# MSS_IO.net
KiCad netlist of a schematic drawn in Altium Designer
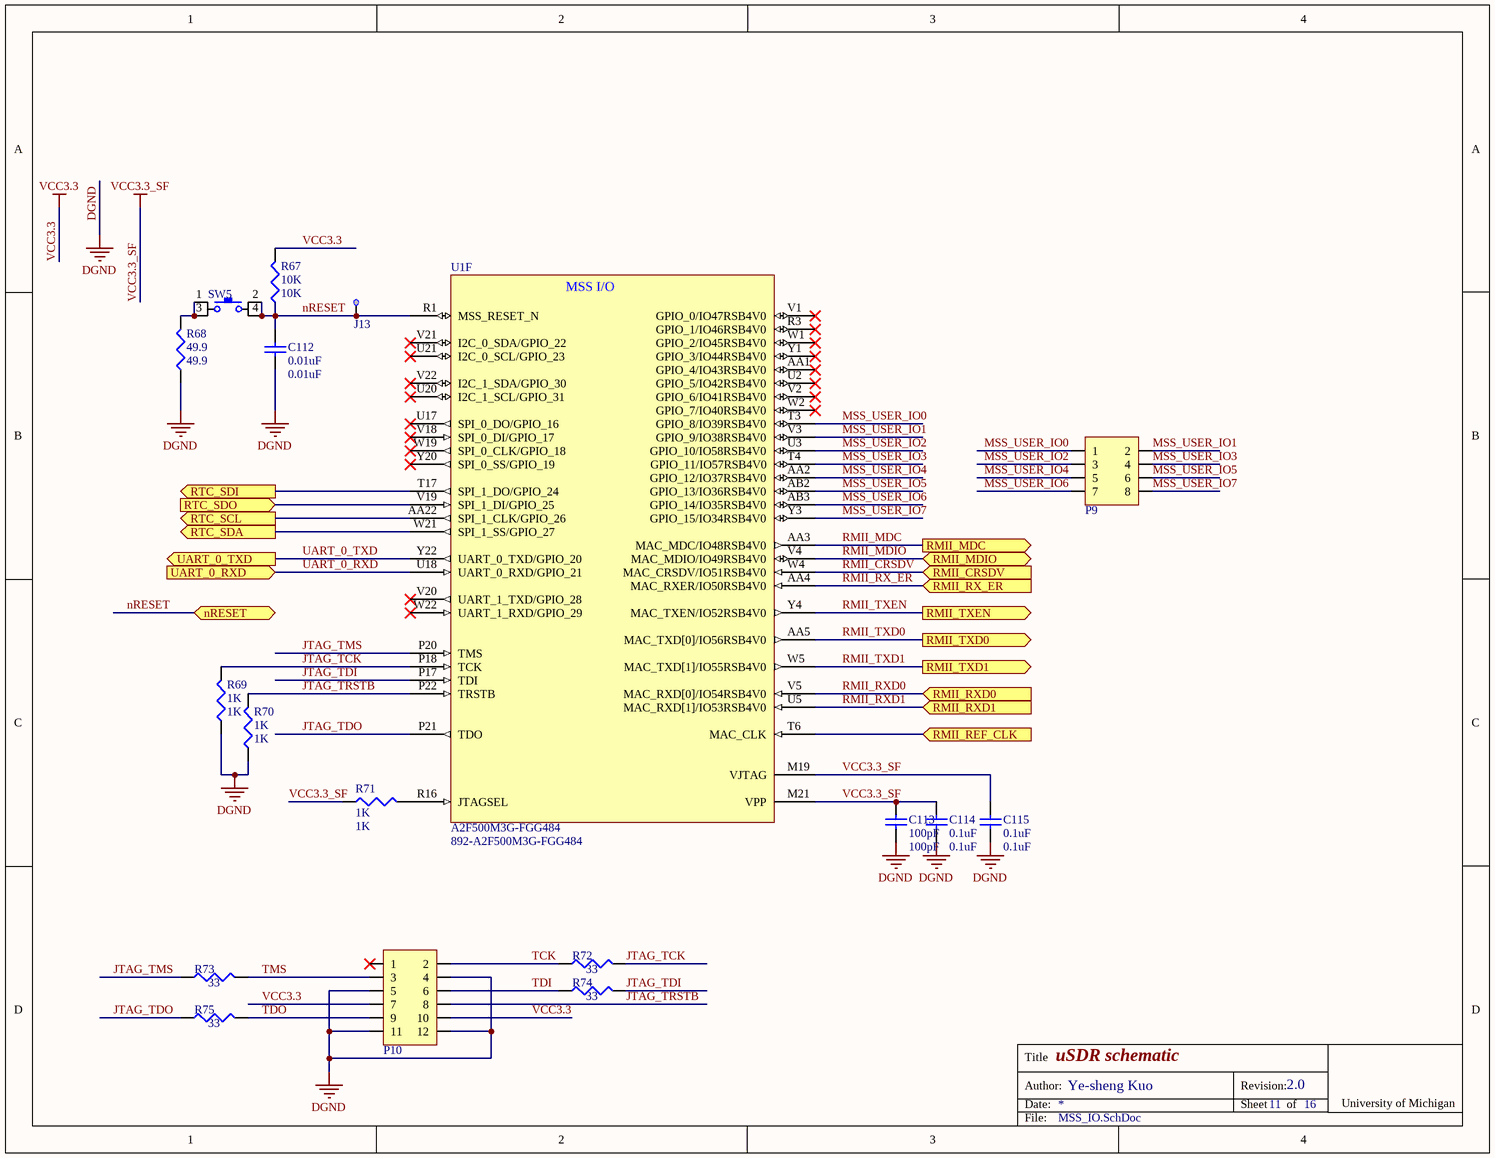
[diagram p0: MSS_IO.SchDoc]

(export (version "E")
  (design (tool "Eeschema 10.0.6"))
  (components
    (comp (ref "C112")
      (value "0.01uF")
      (footprint "0402")
      (description "Capacitor (Semiconductor SIM Model)")
      (fields (field (name "ALTIUM_VALUE") "0.01uF") (field (name "PUBLISHER") "Altium Limited"))
      (libsource (lib "Miscellaneous Devices") (part "Cap Semi"))
    )
    (comp (ref "C113")
      (value "100pF")
      (footprint "0402")
      (description "Capacitor (Semiconductor SIM Model)")
      (fields (field (name "ALTIUM_VALUE") "100pF") (field (name "PUBLISHER") "Altium Limited"))
      (libsource (lib "Miscellaneous Devices") (part "Cap Semi"))
    )
    (comp (ref "C114")
      (value "0.1uF")
      (footprint "0402")
      (description "Capacitor (Semiconductor SIM Model)")
      (fields (field (name "ALTIUM_VALUE") "0.1uF") (field (name "PUBLISHER") "Altium Limited"))
      (libsource (lib "Miscellaneous Devices") (part "Cap Semi"))
    )
    (comp (ref "C115")
      (value "0.1uF")
      (footprint "0402")
      (description "Capacitor (Semiconductor SIM Model)")
      (fields (field (name "ALTIUM_VALUE") "0.1uF") (field (name "PUBLISHER") "Altium Limited"))
      (libsource (lib "Miscellaneous Devices") (part "Cap Semi"))
    )
    (comp (ref "J13")
      (value "5004")
      (footprint "TestPoint")
      (description "TEST POINT PC MINI .040\"D YELLOW")
      (libsource (lib "SDR") (part "TestPoint"))
    )
    (comp (ref "P9")
      (value "2 x 4 header")
      (footprint "2x4 header")
      (description "100 mils standard header")
      (libsource (lib "SDR") (part "2 x 4 header"))
    )
    (comp (ref "P10")
      (value "2 x 6 header")
      (footprint "2x6 header, right angle")
      (description "100 mils standard header")
      (libsource (lib "SDR") (part "2 x 6 header"))
    )
    (comp (ref "R67")
      (value "10K")
      (footprint "0402")
      (description "Resistor")
      (fields (field (name "ALTIUM_VALUE") "10K") (field (name "PUBLISHER") "Altium Limited"))
      (libsource (lib "Miscellaneous Devices") (part "Res3"))
    )
    (comp (ref "R68")
      (value "49.9")
      (footprint "0402")
      (description "Resistor")
      (fields (field (name "ALTIUM_VALUE") "49.9") (field (name "PUBLISHER") "Altium Limited"))
      (libsource (lib "Miscellaneous Devices") (part "Res3"))
    )
    (comp (ref "R69")
      (value "1K")
      (footprint "0402")
      (description "Resistor")
      (fields (field (name "ALTIUM_VALUE") "1K") (field (name "PUBLISHER") "Altium Limited"))
      (libsource (lib "Miscellaneous Devices") (part "Res3"))
    )
    (comp (ref "R70")
      (value "1K")
      (footprint "0402")
      (description "Resistor")
      (fields (field (name "ALTIUM_VALUE") "1K") (field (name "PUBLISHER") "Altium Limited"))
      (libsource (lib "Miscellaneous Devices") (part "Res3"))
    )
    (comp (ref "R71")
      (value "1K")
      (footprint "0402")
      (description "Resistor")
      (fields (field (name "ALTIUM_VALUE") "1K") (field (name "PUBLISHER") "Altium Limited"))
      (libsource (lib "Miscellaneous Devices") (part "Res3"))
    )
    (comp (ref "R72")
      (value "33")
      (footprint "0402")
      (description "Resistor")
      (fields (field (name "PUBLISHER") "Altium Limited"))
      (libsource (lib "Miscellaneous Devices") (part "Res3"))
    )
    (comp (ref "R73")
      (value "33")
      (footprint "0402")
      (description "Resistor")
      (fields (field (name "PUBLISHER") "Altium Limited"))
      (libsource (lib "Miscellaneous Devices") (part "Res3"))
    )
    (comp (ref "R74")
      (value "33")
      (footprint "0402")
      (description "Resistor")
      (fields (field (name "PUBLISHER") "Altium Limited"))
      (libsource (lib "Miscellaneous Devices") (part "Res3"))
    )
    (comp (ref "R75")
      (value "33")
      (footprint "0402")
      (description "Resistor")
      (fields (field (name "PUBLISHER") "Altium Limited"))
      (libsource (lib "Miscellaneous Devices") (part "Res3"))
    )
    (comp (ref "SW5")
      (value "Switch 4-lead")
      (footprint "EVQPA PB")
      (description "Switch")
      (libsource (lib "SDR") (part "Switch 4-lead"))
    )
    (comp (ref "U1")
      (value "A2F500M3G-FGG484")
      (footprint "BGA100P22X22-484N")
      (description "FPGA - Field Programmable Gate Array 500K System Gates")
      (fields (field (name "SUPPLIER PART NUMBER 1") "892-A2F500M3G-FGG484"))
      (libsource (lib "SDR") (part "F2-200_500-FGG484_1"))
    )
  )
  (nets
    (net (code "1") (name "/JTAG_TCK") (class "Default")
      (node (ref "R69") (pin "2") (pinfunction "2_2") (pintype "passive"))
      (node (ref "R72") (pin "2") (pinfunction "2_2") (pintype "passive"))
      (node (ref "U1") (pin "P18") (pinfunction "TCK_P18") (pintype "input"))
    )
    (net (code "2") (name "/JTAG_TDI") (class "Default")
      (node (ref "R74") (pin "2") (pinfunction "2_2") (pintype "passive"))
      (node (ref "U1") (pin "P17") (pinfunction "TDI_P17") (pintype "input"))
    )
    (net (code "3") (name "/JTAG_TDO") (class "Default")
      (node (ref "R75") (pin "1") (pinfunction "1_1") (pintype "passive"))
      (node (ref "U1") (pin "P21") (pinfunction "TDO_P21") (pintype "output"))
    )
    (net (code "4") (name "/JTAG_TMS") (class "Default")
      (node (ref "R73") (pin "1") (pinfunction "1_1") (pintype "passive"))
      (node (ref "U1") (pin "P20") (pinfunction "TMS_P20") (pintype "input"))
    )
    (net (code "5") (name "/JTAG_TRSTB") (class "Default")
      (node (ref "P10") (pin "8") (pinfunction "8_8") (pintype "passive"))
      (node (ref "R70") (pin "2") (pinfunction "2_2") (pintype "passive"))
      (node (ref "U1") (pin "P22") (pinfunction "TRSTB_P22") (pintype "input"))
    )
    (net (code "6") (name "/MSS_USER_IO0") (class "Default")
      (node (ref "P9") (pin "1") (pinfunction "1_1") (pintype "passive"))
      (node (ref "U1") (pin "T3") (pinfunction "GPIO_8/IO39RSB4V0_T3") (pintype "bidirectional"))
    )
    (net (code "7") (name "/MSS_USER_IO1") (class "Default")
      (node (ref "P9") (pin "2") (pinfunction "2_2") (pintype "passive"))
      (node (ref "U1") (pin "V3") (pinfunction "GPIO_9/IO38RSB4V0_V3") (pintype "bidirectional"))
    )
    (net (code "8") (name "/MSS_USER_IO2") (class "Default")
      (node (ref "P9") (pin "3") (pinfunction "3_3") (pintype "passive"))
      (node (ref "U1") (pin "U3") (pinfunction "GPIO_10/IO58RSB4V0_U3") (pintype "bidirectional"))
    )
    (net (code "9") (name "/MSS_USER_IO3") (class "Default")
      (node (ref "P9") (pin "4") (pinfunction "4_4") (pintype "passive"))
      (node (ref "U1") (pin "T4") (pinfunction "GPIO_11/IO57RSB4V0_T4") (pintype "bidirectional"))
    )
    (net (code "10") (name "/MSS_USER_IO4") (class "Default")
      (node (ref "P9") (pin "5") (pinfunction "5_5") (pintype "passive"))
      (node (ref "U1") (pin "AA2") (pinfunction "GPIO_12/IO37RSB4V0_AA2") (pintype "bidirectional"))
    )
    (net (code "11") (name "/MSS_USER_IO5") (class "Default")
      (node (ref "P9") (pin "6") (pinfunction "6_6") (pintype "passive"))
      (node (ref "U1") (pin "AB2") (pinfunction "GPIO_13/IO36RSB4V0_AB2") (pintype "bidirectional"))
    )
    (net (code "12") (name "/MSS_USER_IO6") (class "Default")
      (node (ref "P9") (pin "7") (pinfunction "7_7") (pintype "passive"))
      (node (ref "U1") (pin "AB3") (pinfunction "GPIO_14/IO35RSB4V0_AB3") (pintype "bidirectional"))
    )
    (net (code "13") (name "/MSS_USER_IO7") (class "Default")
      (node (ref "P9") (pin "8") (pinfunction "8_8") (pintype "passive"))
      (node (ref "U1") (pin "Y3") (pinfunction "GPIO_15/IO34RSB4V0_Y3") (pintype "bidirectional"))
    )
    (net (code "14") (name "/RMII_CRSDV") (class "Default")
      (node (ref "U1") (pin "W4") (pinfunction "MAC_CRSDV/IO51RSB4V0_W4") (pintype "input"))
    )
    (net (code "15") (name "/RMII_MDC") (class "Default")
      (node (ref "U1") (pin "AA3") (pinfunction "MAC_MDC/IO48RSB4V0_AA3") (pintype "output"))
    )
    (net (code "16") (name "/RMII_MDIO") (class "Default")
      (node (ref "U1") (pin "V4") (pinfunction "MAC_MDIO/IO49RSB4V0_V4") (pintype "bidirectional"))
    )
    (net (code "17") (name "/RMII_REF_CLK") (class "Default")
      (node (ref "U1") (pin "T6") (pinfunction "MAC_CLK_T6") (pintype "input"))
    )
    (net (code "18") (name "/RMII_RXD0") (class "Default")
      (node (ref "U1") (pin "V5") (pinfunction "MAC_RXD[0]/IO54RSB4V0_V5") (pintype "input"))
    )
    (net (code "19") (name "/RMII_RXD1") (class "Default")
      (node (ref "U1") (pin "U5") (pinfunction "MAC_RXD[1]/IO53RSB4V0_U5") (pintype "input"))
    )
    (net (code "20") (name "/RMII_RX_ER") (class "Default")
      (node (ref "U1") (pin "AA4") (pinfunction "MAC_RXER/IO50RSB4V0_AA4") (pintype "input"))
    )
    (net (code "21") (name "/RMII_TXD0") (class "Default")
      (node (ref "U1") (pin "AA5") (pinfunction "MAC_TXD[0]/IO56RSB4V0_AA5") (pintype "output"))
    )
    (net (code "22") (name "/RMII_TXD1") (class "Default")
      (node (ref "U1") (pin "W5") (pinfunction "MAC_TXD[1]/IO55RSB4V0_W5") (pintype "output"))
    )
    (net (code "23") (name "/RMII_TXEN") (class "Default")
      (node (ref "U1") (pin "Y4") (pinfunction "MAC_TXEN/IO52RSB4V0_Y4") (pintype "output"))
    )
    (net (code "24") (name "/RTC_SCL") (class "Default")
      (node (ref "U1") (pin "AA22") (pinfunction "SPI_1_CLK/GPIO_26_AA22") (pintype "output"))
    )
    (net (code "25") (name "/RTC_SDA") (class "Default")
      (node (ref "U1") (pin "W21") (pinfunction "SPI_1_SS/GPIO_27_W21") (pintype "output"))
    )
    (net (code "26") (name "/RTC_SDI") (class "Default")
      (node (ref "U1") (pin "T17") (pinfunction "SPI_1_DO/GPIO_24_T17") (pintype "output"))
    )
    (net (code "27") (name "/RTC_SDO") (class "Default")
      (node (ref "U1") (pin "V19") (pinfunction "SPI_1_DI/GPIO_25_V19") (pintype "input"))
    )
    (net (code "28") (name "/TCK") (class "Default")
      (node (ref "P10") (pin "2") (pinfunction "2_2") (pintype "passive"))
      (node (ref "R72") (pin "1") (pinfunction "1_1") (pintype "passive"))
    )
    (net (code "29") (name "/TDI") (class "Default")
      (node (ref "P10") (pin "6") (pinfunction "6_6") (pintype "passive"))
      (node (ref "R74") (pin "1") (pinfunction "1_1") (pintype "passive"))
    )
    (net (code "30") (name "/TDO") (class "Default")
      (node (ref "P10") (pin "9") (pinfunction "9_9") (pintype "passive"))
      (node (ref "R75") (pin "2") (pinfunction "2_2") (pintype "passive"))
    )
    (net (code "31") (name "/TMS") (class "Default")
      (node (ref "P10") (pin "3") (pinfunction "3_3") (pintype "passive"))
      (node (ref "R73") (pin "2") (pinfunction "2_2") (pintype "passive"))
    )
    (net (code "32") (name "/UART_0_RXD") (class "Default")
      (node (ref "U1") (pin "U18") (pinfunction "UART_0_RXD/GPIO_21_U18") (pintype "input"))
    )
    (net (code "33") (name "/UART_0_TXD") (class "Default")
      (node (ref "U1") (pin "Y22") (pinfunction "UART_0_TXD/GPIO_20_Y22") (pintype "output"))
    )
    (net (code "34") (name "/nRESET") (class "Default")
      (node (ref "C112") (pin "2") (pinfunction "2_2") (pintype "passive"))
      (node (ref "J13") (pin "1") (pinfunction "TB_1") (pintype "passive"))
      (node (ref "R67") (pin "1") (pinfunction "1_1") (pintype "passive"))
      (node (ref "SW5") (pin "2") (pinfunction "2_2") (pintype "passive"))
      (node (ref "SW5") (pin "4") (pinfunction "4_4") (pintype "passive"))
      (node (ref "U1") (pin "R1") (pinfunction "MSS_RESET_N_R1") (pintype "bidirectional"))
    )
    (net (code "35") (name "DGND") (class "Default")
      (node (ref "C112") (pin "1") (pinfunction "1_1") (pintype "passive"))
      (node (ref "C113") (pin "1") (pinfunction "1_1") (pintype "passive"))
      (node (ref "C114") (pin "1") (pinfunction "1_1") (pintype "passive"))
      (node (ref "C115") (pin "1") (pinfunction "1_1") (pintype "passive"))
      (node (ref "P10") (pin "11") (pinfunction "11_11") (pintype "passive"))
      (node (ref "P10") (pin "12") (pinfunction "12_12") (pintype "passive"))
      (node (ref "P10") (pin "4") (pinfunction "4_4") (pintype "passive"))
      (node (ref "P10") (pin "5") (pinfunction "5_5") (pintype "passive"))
      (node (ref "R68") (pin "1") (pinfunction "1_1") (pintype "passive"))
      (node (ref "R69") (pin "1") (pinfunction "1_1") (pintype "passive"))
      (node (ref "R70") (pin "1") (pinfunction "1_1") (pintype "passive"))
    )
    (net (code "36") (name "Net-(R68-Pad2)") (class "Default")
      (node (ref "R68") (pin "2") (pinfunction "2_2") (pintype "passive"))
      (node (ref "SW5") (pin "1") (pinfunction "1_1") (pintype "passive"))
      (node (ref "SW5") (pin "3") (pinfunction "3_3") (pintype "passive"))
    )
    (net (code "37") (name "Net-(U1F-JTAGSEL)") (class "Default")
      (node (ref "R71") (pin "2") (pinfunction "2_2") (pintype "passive"))
      (node (ref "U1") (pin "R16") (pinfunction "JTAGSEL_R16") (pintype "input"))
    )
    (net (code "38") (name "VCC3.3") (class "Default")
      (node (ref "P10") (pin "10") (pinfunction "10_10") (pintype "passive"))
      (node (ref "P10") (pin "7") (pinfunction "7_7") (pintype "passive"))
      (node (ref "R67") (pin "2") (pinfunction "2_2") (pintype "passive"))
    )
    (net (code "39") (name "VCC3.3_SF") (class "Default")
      (node (ref "C113") (pin "2") (pinfunction "2_2") (pintype "passive"))
      (node (ref "C114") (pin "2") (pinfunction "2_2") (pintype "passive"))
      (node (ref "C115") (pin "2") (pinfunction "2_2") (pintype "passive"))
      (node (ref "R71") (pin "1") (pinfunction "1_1") (pintype "passive"))
      (node (ref "U1") (pin "M19") (pinfunction "VJTAG_M19") (pintype "power_in"))
      (node (ref "U1") (pin "M21") (pinfunction "VPP_M21") (pintype "power_in"))
    )
    (net (code "40") (name "unconnected-(P10-Pad1)") (class "Default")
      (node (ref "P10") (pin "1") (pinfunction "1_1") (pintype "passive+no_connect"))
    )
    (net (code "41") (name "unconnected-(U1F-GPIO_0{slash}IO47RSB4V0-PadV1)") (class "Default")
      (node (ref "U1") (pin "V1") (pinfunction "GPIO_0/IO47RSB4V0_V1") (pintype "bidirectional+no_connect"))
    )
    (net (code "42") (name "unconnected-(U1F-GPIO_1{slash}IO46RSB4V0-PadR3)") (class "Default")
      (node (ref "U1") (pin "R3") (pinfunction "GPIO_1/IO46RSB4V0_R3") (pintype "bidirectional+no_connect"))
    )
    (net (code "43") (name "unconnected-(U1F-GPIO_2{slash}IO45RSB4V0-PadW1)") (class "Default")
      (node (ref "U1") (pin "W1") (pinfunction "GPIO_2/IO45RSB4V0_W1") (pintype "bidirectional+no_connect"))
    )
    (net (code "44") (name "unconnected-(U1F-GPIO_3{slash}IO44RSB4V0-PadY1)") (class "Default")
      (node (ref "U1") (pin "Y1") (pinfunction "GPIO_3/IO44RSB4V0_Y1") (pintype "bidirectional+no_connect"))
    )
    (net (code "45") (name "unconnected-(U1F-GPIO_4{slash}IO43RSB4V0-PadAA1)") (class "Default")
      (node (ref "U1") (pin "AA1") (pinfunction "GPIO_4/IO43RSB4V0_AA1") (pintype "bidirectional+no_connect"))
    )
    (net (code "46") (name "unconnected-(U1F-GPIO_5{slash}IO42RSB4V0-PadU2)") (class "Default")
      (node (ref "U1") (pin "U2") (pinfunction "GPIO_5/IO42RSB4V0_U2") (pintype "bidirectional+no_connect"))
    )
    (net (code "47") (name "unconnected-(U1F-GPIO_6{slash}IO41RSB4V0-PadV2)") (class "Default")
      (node (ref "U1") (pin "V2") (pinfunction "GPIO_6/IO41RSB4V0_V2") (pintype "bidirectional+no_connect"))
    )
    (net (code "48") (name "unconnected-(U1F-GPIO_7{slash}IO40RSB4V0-PadW2)") (class "Default")
      (node (ref "U1") (pin "W2") (pinfunction "GPIO_7/IO40RSB4V0_W2") (pintype "bidirectional+no_connect"))
    )
    (net (code "49") (name "unconnected-(U1F-I2C_0_SCL{slash}GPIO_23-PadU21)") (class "Default")
      (node (ref "U1") (pin "U21") (pinfunction "I2C_0_SCL/GPIO_23_U21") (pintype "bidirectional+no_connect"))
    )
    (net (code "50") (name "unconnected-(U1F-I2C_0_SDA{slash}GPIO_22-PadV21)") (class "Default")
      (node (ref "U1") (pin "V21") (pinfunction "I2C_0_SDA/GPIO_22_V21") (pintype "bidirectional+no_connect"))
    )
    (net (code "51") (name "unconnected-(U1F-I2C_1_SCL{slash}GPIO_31-PadU20)") (class "Default")
      (node (ref "U1") (pin "U20") (pinfunction "I2C_1_SCL/GPIO_31_U20") (pintype "bidirectional+no_connect"))
    )
    (net (code "52") (name "unconnected-(U1F-I2C_1_SDA{slash}GPIO_30-PadV22)") (class "Default")
      (node (ref "U1") (pin "V22") (pinfunction "I2C_1_SDA/GPIO_30_V22") (pintype "bidirectional+no_connect"))
    )
    (net (code "53") (name "unconnected-(U1F-SPI_0_CLK{slash}GPIO_18-PadW19)") (class "Default")
      (node (ref "U1") (pin "W19") (pinfunction "SPI_0_CLK/GPIO_18_W19") (pintype "output+no_connect"))
    )
    (net (code "54") (name "unconnected-(U1F-SPI_0_DI{slash}GPIO_17-PadV18)") (class "Default")
      (node (ref "U1") (pin "V18") (pinfunction "SPI_0_DI/GPIO_17_V18") (pintype "input+no_connect"))
    )
    (net (code "55") (name "unconnected-(U1F-SPI_0_DO{slash}GPIO_16-PadU17)") (class "Default")
      (node (ref "U1") (pin "U17") (pinfunction "SPI_0_DO/GPIO_16_U17") (pintype "output+no_connect"))
    )
    (net (code "56") (name "unconnected-(U1F-SPI_0_SS{slash}GPIO_19-PadY20)") (class "Default")
      (node (ref "U1") (pin "Y20") (pinfunction "SPI_0_SS/GPIO_19_Y20") (pintype "output+no_connect"))
    )
    (net (code "57") (name "unconnected-(U1F-UART_1_RXD{slash}GPIO_29-PadW22)") (class "Default")
      (node (ref "U1") (pin "W22") (pinfunction "UART_1_RXD/GPIO_29_W22") (pintype "input+no_connect"))
    )
    (net (code "58") (name "unconnected-(U1F-UART_1_TXD{slash}GPIO_28-PadV20)") (class "Default")
      (node (ref "U1") (pin "V20") (pinfunction "UART_1_TXD/GPIO_28_V20") (pintype "output+no_connect"))
    )
  )
)
